# rocketSoldering.net
KiCad netlist of a schematic drawn in EAGLE
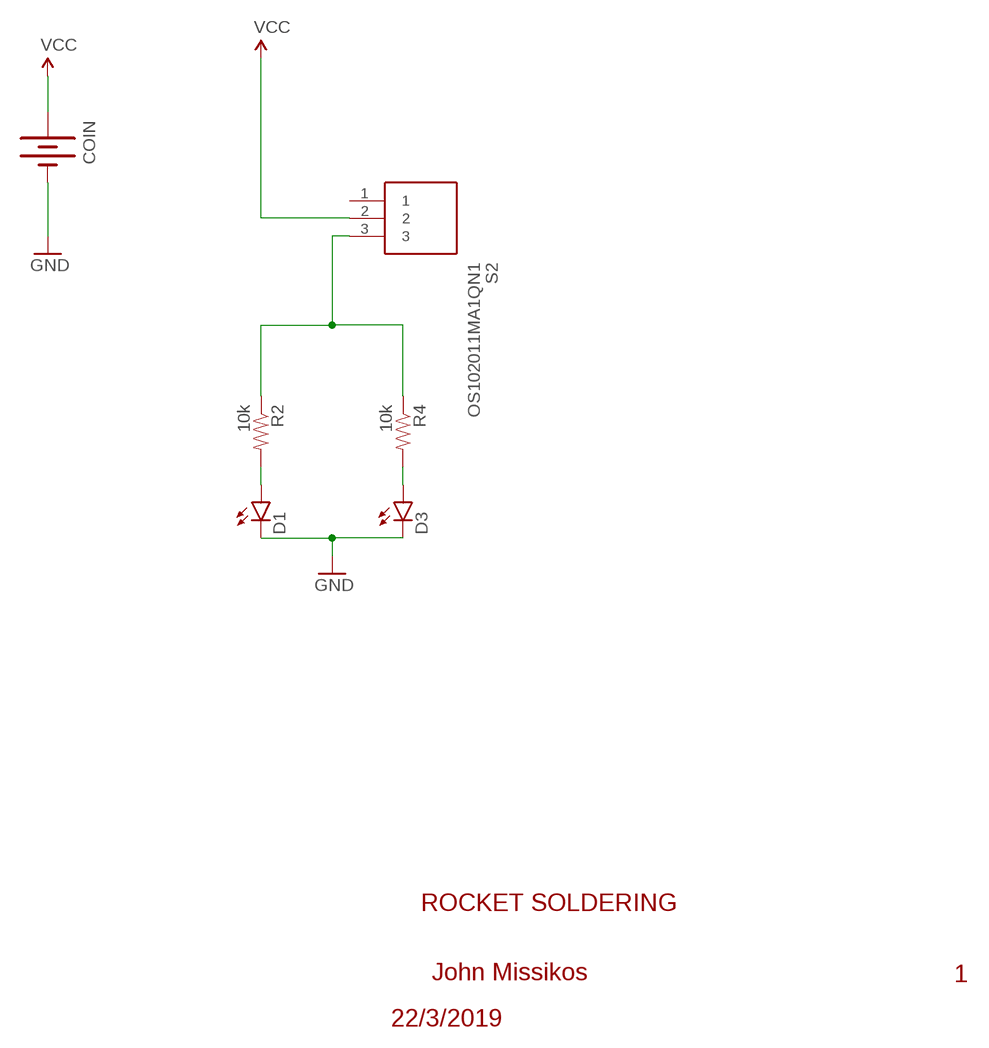
[diagram p0: schematic, sheet 1]

(export (version "E")
  (design (tool "Eeschema 10.0.6"))
  (components
    (comp (ref "COIN")
      (value "BATTERY_20MM20PTH")
      (footprint "eagle-import:BATTCOM_20MM_PTH")
      (libsource (lib "eagle-import") (part "BATTERY_20MM20PTH"))
    )
    (comp (ref "D1")
      (value "LED5MM")
      (footprint "eagle-import:LED5MM")
      (libsource (lib "eagle-import") (part "LED5MM"))
    )
    (comp (ref "D3")
      (value "LED5MM")
      (footprint "eagle-import:LED5MM")
      (libsource (lib "eagle-import") (part "LED5MM"))
    )
    (comp (ref "R2")
      (value "10k")
      (footprint "eagle-import:AXIAL-0.3")
      (libsource (lib "eagle-import") (part "RESISTORAXIAL-0.3"))
    )
    (comp (ref "R4")
      (value "10k")
      (footprint "eagle-import:AXIAL-0.3")
      (libsource (lib "eagle-import") (part "RESISTORAXIAL-0.3"))
    )
    (comp (ref "S2")
      (value "OS102011MA1QN1")
      (footprint "eagle-import:OS102011MA1QN1")
      (fields
        (field (name "MOUSER_PART_NUMBER") "611-OS102011MA1QN1")
        (field (name "RS_PART_NUMBER") "7874855")
      )
      (libsource (lib "eagle-import") (part "OS102011MA1QN1"))
    )
  )
  (nets
    (net (code "1") (name "GND") (class "Default")
      (node (ref "COIN") (pin "2") (pinfunction "-_2") (pintype "power_in"))
      (node (ref "D1") (pin "K") (pinfunction "C_K") (pintype "passive"))
      (node (ref "D3") (pin "K") (pinfunction "C_K") (pintype "passive"))
    )
    (net (code "2") (name "Net-(R2-1)") (class "Default")
      (node (ref "R2") (pin "P$1") (pinfunction "1_P$1") (pintype "passive"))
      (node (ref "R4") (pin "P$1") (pinfunction "1_P$1") (pintype "passive"))
      (node (ref "S2") (pin "3") (pinfunction "3_3") (pintype "bidirectional"))
    )
    (net (code "3") (name "Net-(R2-2)") (class "Default")
      (node (ref "D1") (pin "A") (pinfunction "A_A") (pintype "passive"))
      (node (ref "R2") (pin "P$2") (pinfunction "2_P$2") (pintype "passive"))
    )
    (net (code "4") (name "Net-(R4-2)") (class "Default")
      (node (ref "D3") (pin "A") (pinfunction "A_A") (pintype "passive"))
      (node (ref "R4") (pin "P$2") (pinfunction "2_P$2") (pintype "passive"))
    )
    (net (code "5") (name "VCC") (class "Default")
      (node (ref "COIN") (pin "1") (pinfunction "+_1") (pintype "power_in"))
      (node (ref "S2") (pin "2") (pinfunction "2_2") (pintype "bidirectional"))
    )
    (net (code "6") (name "unconnected-(S2-Pad1)") (class "Default")
      (node (ref "S2") (pin "1") (pinfunction "1_1") (pintype "bidirectional"))
    )
  )
)
